# Curr_Volt_Measurement.net
KiCad netlist of a schematic drawn in Altium Designer
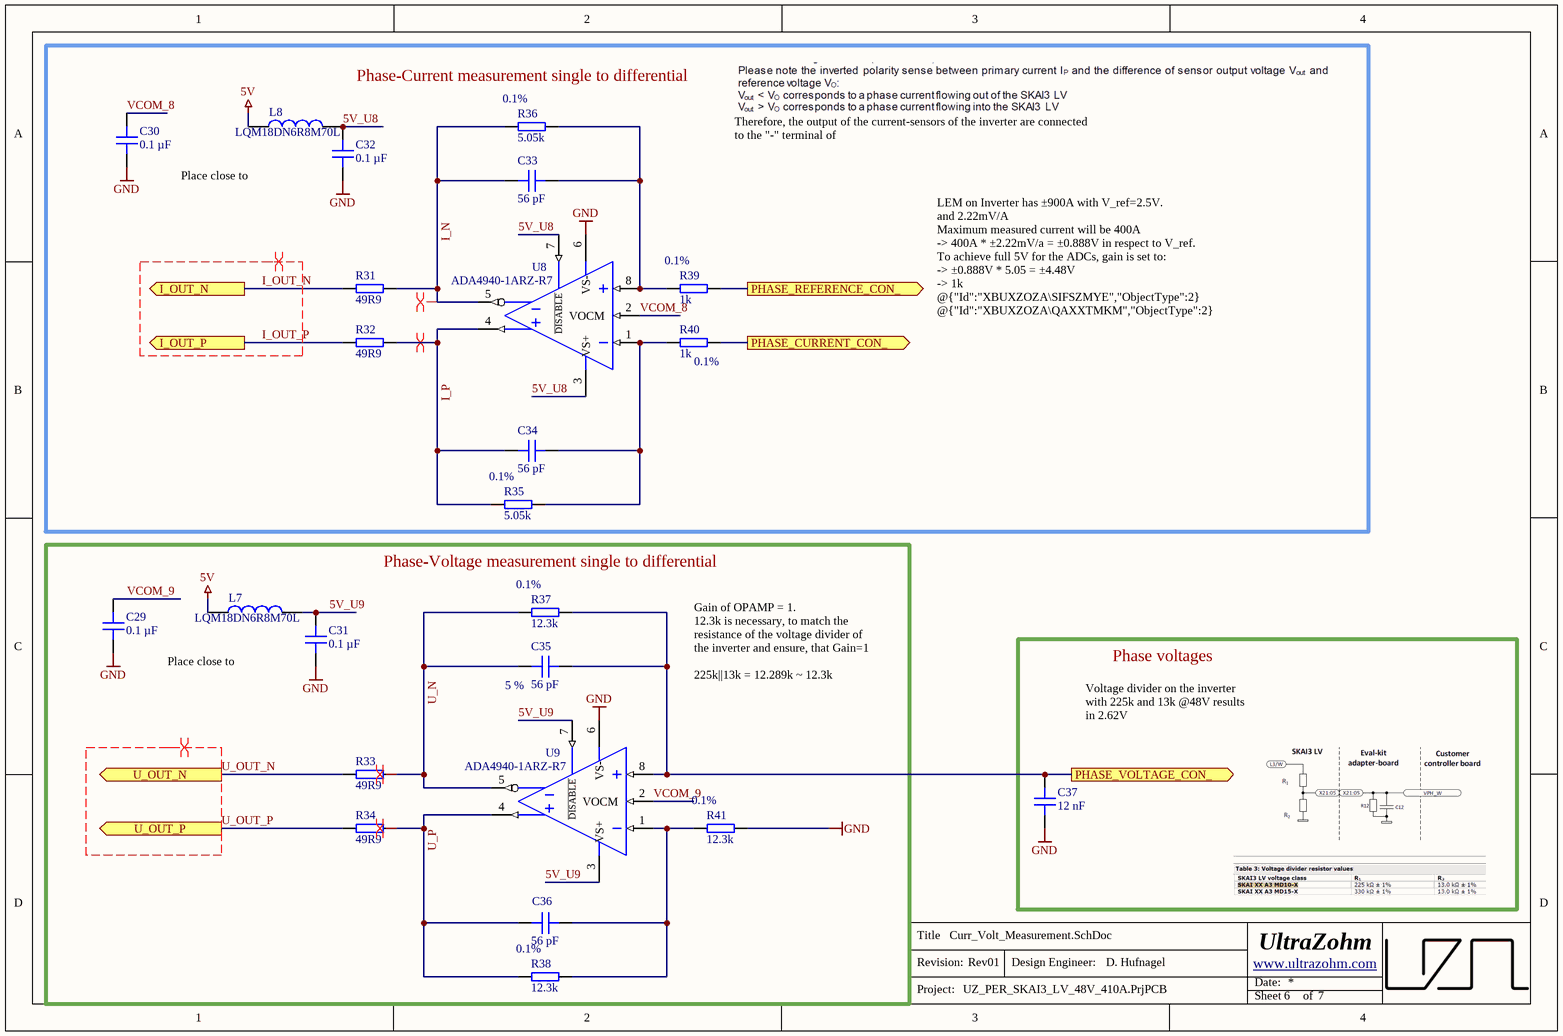
[diagram p0: Curr_Volt_Measurement.SchDoc]

(export (version "E")
  (design (tool "Eeschema 10.0.6"))
  (components
    (comp (ref "C29")
      (value "0.1 µF")
      (footprint "C_0603")
      (description "Capacitor 0603, 50 VDC, 0.1 µF, X7R")
      (fields
        (field (name "MANUFACTURER PART NUMBER") "C0603X104K5RAC7411")
        (field (name "MANUFACTURER") "KEMET")
        (field (name "CREATED FROM") "MGremer")
      )
      (libsource (lib "user") (part "Capacitor"))
    )
    (comp (ref "C30")
      (value "0.1 µF")
      (footprint "C_0603")
      (description "Capacitor 0603, 50 VDC, 0.1 µF, X7R")
      (fields
        (field (name "MANUFACTURER PART NUMBER") "C0603X104K5RAC7411")
        (field (name "MANUFACTURER") "KEMET")
        (field (name "CREATED FROM") "MGremer")
      )
      (libsource (lib "user") (part "Capacitor"))
    )
    (comp (ref "C31")
      (value "0.1 µF")
      (footprint "C_0603")
      (description "Capacitor 0603, 50 VDC, 0.1 µF, X7R")
      (fields
        (field (name "MANUFACTURER PART NUMBER") "C0603X104K5RAC7411")
        (field (name "MANUFACTURER") "KEMET")
        (field (name "CREATED FROM") "MGremer")
      )
      (libsource (lib "user") (part "Capacitor"))
    )
    (comp (ref "C32")
      (value "0.1 µF")
      (footprint "C_0603")
      (description "Capacitor 0603, 50 VDC, 0.1 µF, X7R")
      (fields
        (field (name "MANUFACTURER PART NUMBER") "C0603X104K5RAC7411")
        (field (name "MANUFACTURER") "KEMET")
        (field (name "CREATED FROM") "MGremer")
      )
      (libsource (lib "user") (part "Capacitor"))
    )
    (comp (ref "C33")
      (value "56 pF")
      (footprint "C_0603")
      (description "Capacitor 0603, 50 VDC, 56 pF, C0G")
      (fields
        (field (name "MANUFACTURER PART NUMBER") "CL10C560JB8NNNC")
        (field (name "MANUFACTURER") "Samsung Electro-Mechanics")
        (field (name "CREATED FROM") "DHufnagel")
      )
      (libsource (lib "user") (part "Capacitor"))
    )
    (comp (ref "C34")
      (value "56 pF")
      (footprint "C_0603")
      (description "Capacitor 0603, 50 VDC, 56 pF, C0G")
      (fields
        (field (name "MANUFACTURER PART NUMBER") "CL10C560JB8NNNC")
        (field (name "MANUFACTURER") "Samsung Electro-Mechanics")
        (field (name "CREATED FROM") "DHufnagel")
      )
      (libsource (lib "user") (part "Capacitor"))
    )
    (comp (ref "C35")
      (value "56 pF")
      (footprint "C_0603")
      (description "Capacitor 0603, 50 VDC, 56 pF, C0G")
      (fields
        (field (name "MANUFACTURER PART NUMBER") "CL10C560JB8NNNC")
        (field (name "MANUFACTURER") "Samsung Electro-Mechanics")
        (field (name "TOLERANCE") "5 %")
        (field (name "CREATED FROM") "DHufnagel")
      )
      (libsource (lib "user") (part "Capacitor"))
    )
    (comp (ref "C36")
      (value "56 pF")
      (footprint "C_0603")
      (description "Capacitor 0603, 50 VDC, 56 pF, C0G")
      (fields
        (field (name "MANUFACTURER PART NUMBER") "CL10C560JB8NNNC")
        (field (name "MANUFACTURER") "Samsung Electro-Mechanics")
        (field (name "CREATED FROM") "DHufnagel")
      )
      (libsource (lib "user") (part "Capacitor"))
    )
    (comp (ref "C37")
      (value "12 nF")
      (footprint "C_0603")
      (description "Capacitor 0603, 16 VDC, 12 nF, X7R")
      (fields
        (field (name "MANUFACTURER PART NUMBER") "CC0603KRX7R7BB123")
        (field (name "MANUFACTURER") "Yageo")
        (field (name "CREATED FROM") "MGremer")
      )
      (libsource (lib "user") (part "Capacitor"))
    )
    (comp (ref "L7")
      (value "LQM18DN6R8M70L")
      (footprint "INDC1608X95N")
      (description "6.8µH, 120mA, 0603, 740mOhm, 20%")
      (fields
        (field (name "MF") "EPCOS / TDK")
        (field (name "MPN") "B82464G4154M")
        (field (name "CREATED FROM") "DHufnagel")
      )
      (libsource (lib "user") (part "B82464G4154M"))
    )
    (comp (ref "L8")
      (value "LQM18DN6R8M70L")
      (footprint "INDC1608X95N")
      (description "6.8µH, 120mA, 0603, 740mOhm, 20%")
      (fields
        (field (name "MF") "EPCOS / TDK")
        (field (name "MPN") "B82464G4154M")
        (field (name "CREATED FROM") "DHufnagel")
      )
      (libsource (lib "user") (part "B82464G4154M"))
    )
    (comp (ref "R31")
      (value "49R9")
      (footprint "RES 0603_1608")
      (description "SMD resistor 1%")
      (fields
        (field (name "MANUFACTURER PART NUMBER") "RK73H1JTTD49R9F")
        (field (name "MANUFACTURER") "KOA Speer")
        (field (name "CREATED FROM") "DHufnagel")
      )
      (libsource (lib "user") (part "Resistor"))
    )
    (comp (ref "R32")
      (value "49R9")
      (footprint "RES 0603_1608")
      (description "SMD resistor 1%")
      (fields
        (field (name "MANUFACTURER PART NUMBER") "RK73H1JTTD49R9F")
        (field (name "MANUFACTURER") "KOA Speer")
        (field (name "CREATED FROM") "DHufnagel")
      )
      (libsource (lib "user") (part "Resistor"))
    )
    (comp (ref "R33")
      (value "49R9")
      (footprint "RES 0603_1608")
      (description "SMD resistor 1%")
      (fields
        (field (name "MANUFACTURER PART NUMBER") "RK73H1JTTD49R9F")
        (field (name "MANUFACTURER") "KOA Speer")
        (field (name "CREATED FROM") "DHufnagel")
      )
      (libsource (lib "user") (part "Resistor"))
    )
    (comp (ref "R34")
      (value "49R9")
      (footprint "RES 0603_1608")
      (description "SMD resistor 1%")
      (fields
        (field (name "MANUFACTURER PART NUMBER") "RK73H1JTTD49R9F")
        (field (name "MANUFACTURER") "KOA Speer")
        (field (name "CREATED FROM") "DHufnagel")
      )
      (libsource (lib "user") (part "Resistor"))
    )
    (comp (ref "R35")
      (value "5.05k")
      (footprint "RES 0603_1608")
      (description "SMD resistor 0.1%")
      (fields
        (field (name "MANUFACTURER PART NUMBER") "TNPW06035K05BEEA")
        (field (name "MANUFACTURER") "Vishay")
        (field (name "TOLERANCE") "0.1%")
        (field (name "CREATED FROM") "DHufnagel")
      )
      (libsource (lib "user") (part "Resistor"))
    )
    (comp (ref "R36")
      (value "5.05k")
      (footprint "RES 0603_1608")
      (description "SMD resistor 0.1%")
      (fields
        (field (name "MANUFACTURER PART NUMBER") "TNPW06035K05BEEA")
        (field (name "MANUFACTURER") "Vishay")
        (field (name "TOLERANCE") "0.1%")
        (field (name "CREATED FROM") "DHufnagel")
      )
      (libsource (lib "user") (part "Resistor"))
    )
    (comp (ref "R37")
      (value "12.3k")
      (footprint "RES 0603_1608")
      (description "SMD resistor E24 series 12 kOhms 100mW 0603 1%")
      (fields
        (field (name "MANUFACTURER PART NUMBER") "RT0603BRD0712K3L")
        (field (name "MANUFACTURER") "YAGEO")
        (field (name "TOLERANCE") "0.1%")
        (field (name "CREATED FROM") "DHufnagel")
      )
      (libsource (lib "user") (part "Resistor"))
    )
    (comp (ref "R38")
      (value "12.3k")
      (footprint "RES 0603_1608")
      (description "SMD resistor E24 series 12 kOhms 100mW 0603 1%")
      (fields
        (field (name "MANUFACTURER PART NUMBER") "RT0603BRD0712K3L")
        (field (name "MANUFACTURER") "YAGEO")
        (field (name "TOLERANCE") "0.1%")
        (field (name "CREATED FROM") "DHufnagel")
      )
      (libsource (lib "user") (part "Resistor"))
    )
    (comp (ref "R39")
      (value "1k")
      (footprint "RES 0603_1608")
      (description "SMD resistor 0.1%")
      (fields
        (field (name "MANUFACTURER PART NUMBER") "PCF-W0603LF-03-1001-B-P-LT")
        (field (name "MANUFACTURER") "IRC / TT Electronics")
        (field (name "TOLERANCE") "0.1%")
        (field (name "CREATED FROM") "MGremer")
      )
      (libsource (lib "user") (part "Resistor"))
    )
    (comp (ref "R40")
      (value "1k")
      (footprint "RES 0603_1608")
      (description "SMD resistor 0.1%")
      (fields
        (field (name "MANUFACTURER PART NUMBER") "PCF-W0603LF-03-1001-B-P-LT")
        (field (name "MANUFACTURER") "IRC / TT Electronics")
        (field (name "TOLERANCE") "0.1%")
        (field (name "CREATED FROM") "MGremer")
      )
      (libsource (lib "user") (part "Resistor"))
    )
    (comp (ref "R41")
      (value "12.3k")
      (footprint "RES 0603_1608")
      (description "SMD resistor E24 series 12 kOhms 100mW 0603 1%")
      (fields
        (field (name "MANUFACTURER PART NUMBER") "RT0603BRD0712K3L")
        (field (name "MANUFACTURER") "YAGEO")
        (field (name "TOLERANCE") "0.1%")
        (field (name "CREATED FROM") "DHufnagel")
      )
      (libsource (lib "user") (part "Resistor"))
    )
    (comp (ref "U8")
      (value "ADA4940-1ARZ-R7")
      (footprint "SOT127P600X175-8N")
      (description "Fully Differential Amplifier, Ultralow-Power,Low Distortion, 260-MHz")
      (fields
        (field (name "MANUFACTURER") "Analog Devices")
        (field (name "LCSC PART NUMBER") "C730049")
        (field (name "CREATED FROM") "DHufnagel")
      )
      (libsource (lib "user") (part "ADA4940-1ARZ"))
    )
    (comp (ref "U9")
      (value "ADA4940-1ARZ-R7")
      (footprint "SOT127P600X175-8N")
      (description "Fully Differential Amplifier, Ultralow-Power,Low Distortion, 260-MHz")
      (fields
        (field (name "MANUFACTURER") "Analog Devices")
        (field (name "LCSC PART NUMBER") "C730049")
        (field (name "CREATED FROM") "DHufnagel")
      )
      (libsource (lib "user") (part "ADA4940-1ARZ"))
    )
  )
  (nets
    (net (code "1") (name "/5V_U8") (class "Default")
      (node (ref "C32") (pin "2") (pinfunction "2_2") (pintype "passive"))
      (node (ref "L8") (pin "2") (pinfunction "2_2") (pintype "passive"))
      (node (ref "U8") (pin "3") (pinfunction "VS+_3") (pintype "power_in"))
      (node (ref "U8") (pin "7") (pinfunction "~{DISABLE}_7") (pintype "input"))
    )
    (net (code "2") (name "/5V_U9") (class "Default")
      (node (ref "C31") (pin "2") (pinfunction "2_2") (pintype "passive"))
      (node (ref "L7") (pin "2") (pinfunction "2_2") (pintype "passive"))
      (node (ref "U9") (pin "3") (pinfunction "VS+_3") (pintype "power_in"))
      (node (ref "U9") (pin "7") (pinfunction "~{DISABLE}_7") (pintype "input"))
    )
    (net (code "3") (name "/I_N") (class "Default")
      (node (ref "C33") (pin "1") (pinfunction "1_1") (pintype "passive"))
      (node (ref "R31") (pin "2") (pinfunction "2_2") (pintype "passive"))
      (node (ref "R36") (pin "1") (pinfunction "1_1") (pintype "passive"))
      (node (ref "U8") (pin "5") (pinfunction "VOUT-_5") (pintype "output"))
    )
    (net (code "4") (name "/I_OUT_N") (class "Default")
      (node (ref "R31") (pin "1") (pinfunction "1_1") (pintype "passive"))
    )
    (net (code "5") (name "/I_OUT_P") (class "Default")
      (node (ref "R32") (pin "1") (pinfunction "1_1") (pintype "passive"))
    )
    (net (code "6") (name "/I_P") (class "Default")
      (node (ref "C34") (pin "1") (pinfunction "1_1") (pintype "passive"))
      (node (ref "R32") (pin "2") (pinfunction "2_2") (pintype "passive"))
      (node (ref "R35") (pin "1") (pinfunction "1_1") (pintype "passive"))
      (node (ref "U8") (pin "4") (pinfunction "VOUT+_4") (pintype "output"))
    )
    (net (code "7") (name "/PHASE_CURRENT_CON_") (class "Default")
      (node (ref "R40") (pin "2") (pinfunction "2_2") (pintype "passive"))
    )
    (net (code "8") (name "/PHASE_REFERENCE_CON_") (class "Default")
      (node (ref "R39") (pin "2") (pinfunction "2_2") (pintype "passive"))
    )
    (net (code "9") (name "/PHASE_VOLTAGE_CON_") (class "Default")
      (node (ref "C35") (pin "2") (pinfunction "2_2") (pintype "passive"))
      (node (ref "C37") (pin "2") (pinfunction "2_2") (pintype "passive"))
      (node (ref "R37") (pin "2") (pinfunction "2_2") (pintype "passive"))
      (node (ref "U9") (pin "8") (pinfunction "VIN+_8") (pintype "input"))
    )
    (net (code "10") (name "/U_N") (class "Default")
      (node (ref "C35") (pin "1") (pinfunction "1_1") (pintype "passive"))
      (node (ref "R33") (pin "2") (pinfunction "2_2") (pintype "passive"))
      (node (ref "R37") (pin "1") (pinfunction "1_1") (pintype "passive"))
      (node (ref "U9") (pin "5") (pinfunction "VOUT-_5") (pintype "output"))
    )
    (net (code "11") (name "/U_OUT_N") (class "Default")
      (node (ref "R33") (pin "1") (pinfunction "1_1") (pintype "passive"))
    )
    (net (code "12") (name "/U_OUT_P") (class "Default")
      (node (ref "R34") (pin "1") (pinfunction "1_1") (pintype "passive"))
    )
    (net (code "13") (name "/U_P") (class "Default")
      (node (ref "C36") (pin "1") (pinfunction "1_1") (pintype "passive"))
      (node (ref "R34") (pin "2") (pinfunction "2_2") (pintype "passive"))
      (node (ref "R38") (pin "1") (pinfunction "1_1") (pintype "passive"))
      (node (ref "U9") (pin "4") (pinfunction "VOUT+_4") (pintype "output"))
    )
    (net (code "14") (name "/VCOM_8") (class "Default")
      (node (ref "C30") (pin "2") (pinfunction "2_2") (pintype "passive"))
      (node (ref "U8") (pin "2") (pinfunction "VOCM_2") (pintype "input"))
    )
    (net (code "15") (name "/VCOM_9") (class "Default")
      (node (ref "C29") (pin "2") (pinfunction "2_2") (pintype "passive"))
      (node (ref "U9") (pin "2") (pinfunction "VOCM_2") (pintype "input"))
    )
    (net (code "16") (name "5V") (class "Default")
      (node (ref "L7") (pin "1") (pinfunction "1_1") (pintype "passive"))
      (node (ref "L8") (pin "1") (pinfunction "1_1") (pintype "passive"))
    )
    (net (code "17") (name "GND") (class "Default")
      (node (ref "C29") (pin "1") (pinfunction "1_1") (pintype "passive"))
      (node (ref "C30") (pin "1") (pinfunction "1_1") (pintype "passive"))
      (node (ref "C31") (pin "1") (pinfunction "1_1") (pintype "passive"))
      (node (ref "C32") (pin "1") (pinfunction "1_1") (pintype "passive"))
      (node (ref "C37") (pin "1") (pinfunction "1_1") (pintype "passive"))
      (node (ref "R41") (pin "2") (pinfunction "2_2") (pintype "passive"))
      (node (ref "U8") (pin "6") (pinfunction "VS-_6") (pintype "power_in"))
      (node (ref "U9") (pin "6") (pinfunction "VS-_6") (pintype "power_in"))
    )
    (net (code "18") (name "Net-(U8-VIN+)") (class "Default")
      (node (ref "C33") (pin "2") (pinfunction "2_2") (pintype "passive"))
      (node (ref "R36") (pin "2") (pinfunction "2_2") (pintype "passive"))
      (node (ref "R39") (pin "1") (pinfunction "1_1") (pintype "passive"))
      (node (ref "U8") (pin "8") (pinfunction "VIN+_8") (pintype "input"))
    )
    (net (code "19") (name "Net-(U8-VIN-)") (class "Default")
      (node (ref "C34") (pin "2") (pinfunction "2_2") (pintype "passive"))
      (node (ref "R35") (pin "2") (pinfunction "2_2") (pintype "passive"))
      (node (ref "R40") (pin "1") (pinfunction "1_1") (pintype "passive"))
      (node (ref "U8") (pin "1") (pinfunction "VIN-_1") (pintype "input"))
    )
    (net (code "20") (name "Net-(U9-VIN-)") (class "Default")
      (node (ref "C36") (pin "2") (pinfunction "2_2") (pintype "passive"))
      (node (ref "R38") (pin "2") (pinfunction "2_2") (pintype "passive"))
      (node (ref "R41") (pin "1") (pinfunction "1_1") (pintype "passive"))
      (node (ref "U9") (pin "1") (pinfunction "VIN-_1") (pintype "input"))
    )
  )
)
